# LCDSerialBackpack.net
KiCad netlist of a schematic drawn in EAGLE
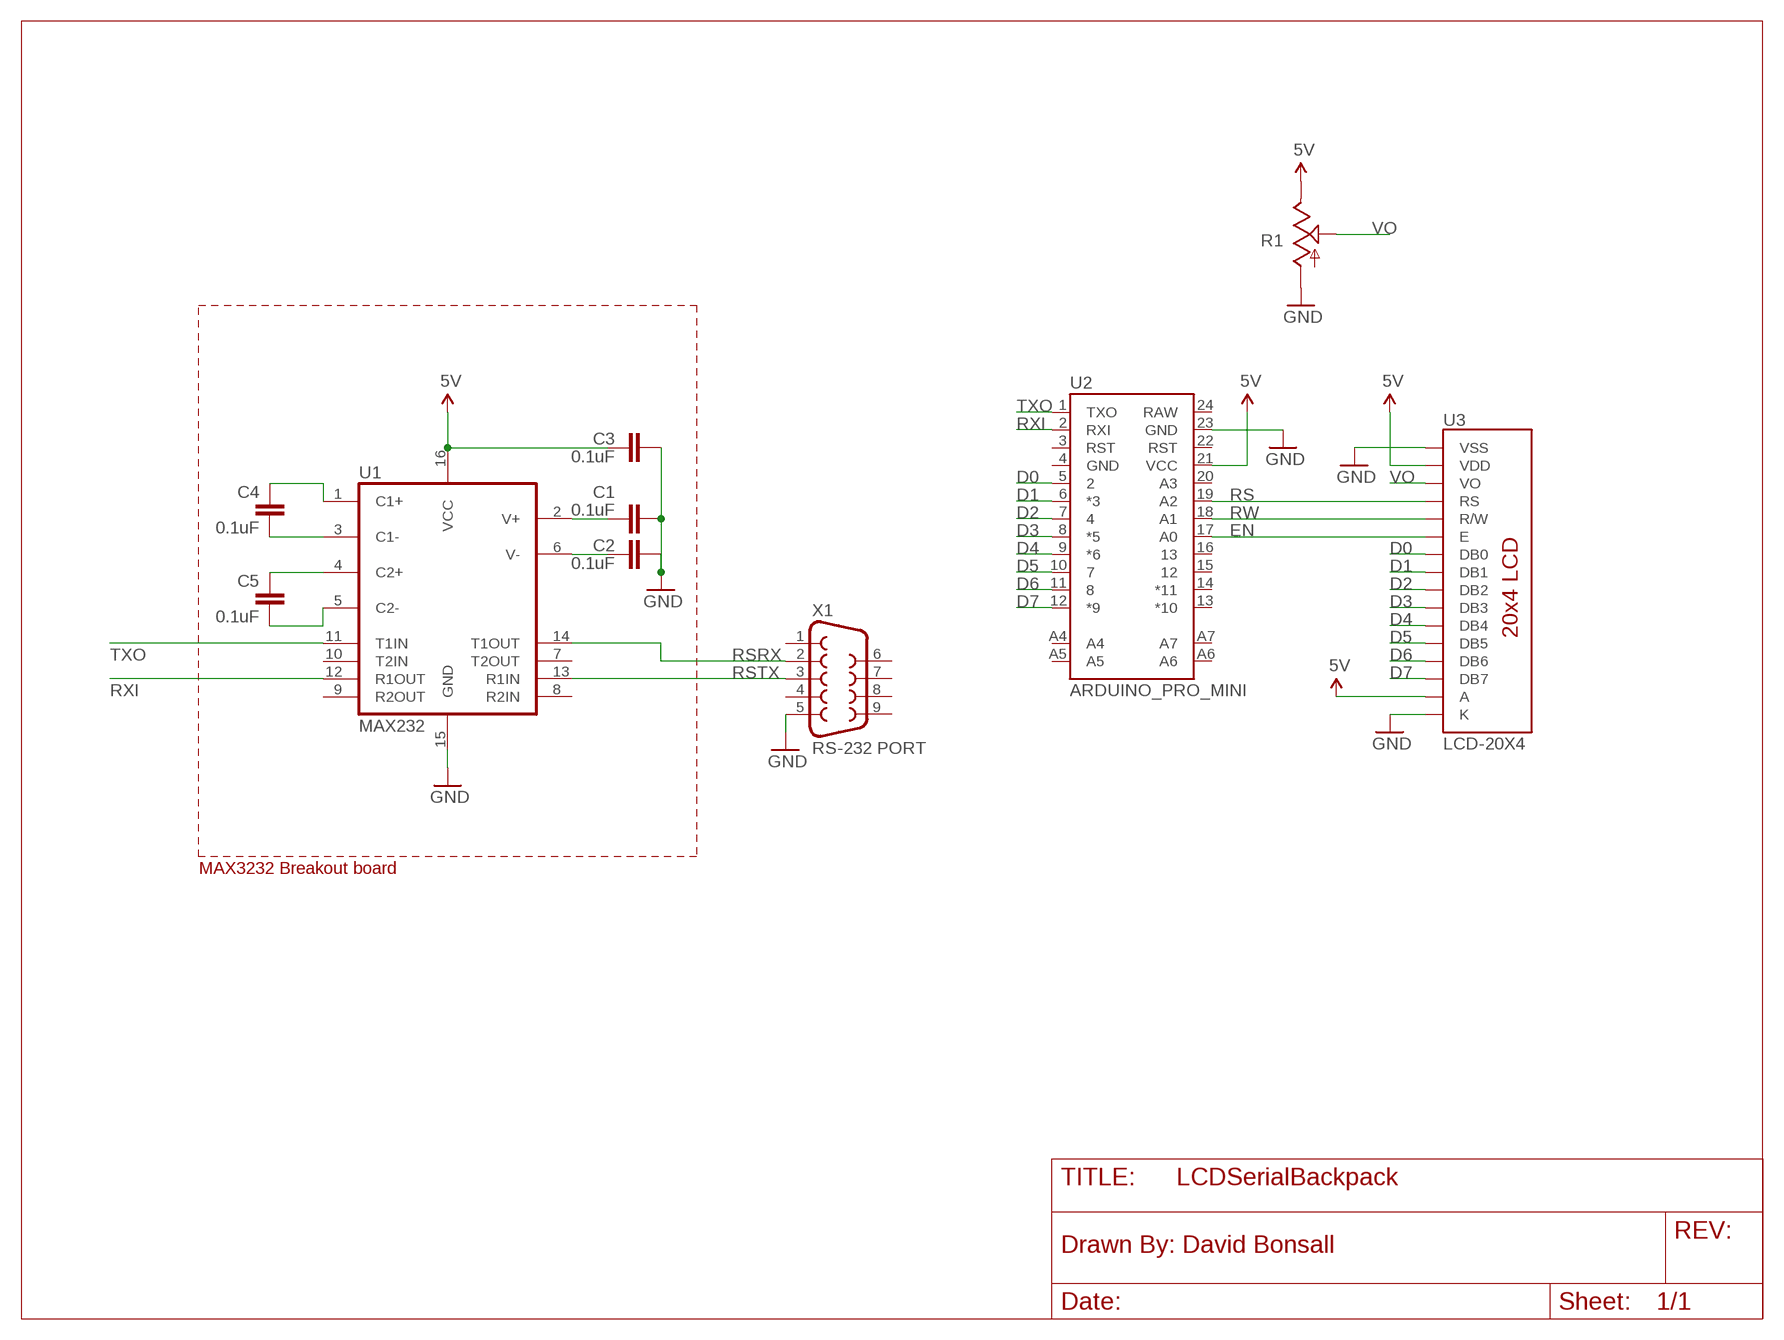
[diagram p0: schematic, sheet 1]

(export (version "E")
  (design (tool "Eeschema 10.0.6"))
  (components
    (comp (ref "C1")
      (value "0.1uF")
      (footprint "eagle-import:0402-CAP")
      (libsource (lib "eagle-import") (part ".1UF-CER"))
    )
    (comp (ref "C2")
      (value "0.1uF")
      (footprint "eagle-import:0402-CAP")
      (libsource (lib "eagle-import") (part ".1UF-CER"))
    )
    (comp (ref "C3")
      (value "0.1uF")
      (footprint "eagle-import:0402-CAP")
      (libsource (lib "eagle-import") (part ".1UF-CER"))
    )
    (comp (ref "C4")
      (value "0.1uF")
      (footprint "eagle-import:0402-CAP")
      (libsource (lib "eagle-import") (part ".1UF-CER"))
    )
    (comp (ref "C5")
      (value "0.1uF")
      (footprint "eagle-import:0402-CAP")
      (libsource (lib "eagle-import") (part ".1UF-CER"))
    )
    (comp (ref "R1")
      (value "POT100K_3362U")
      (footprint "eagle-import:3362U")
      (libsource (lib "eagle-import") (part "POT100K_3362U"))
    )
    (comp (ref "U1")
      (value "MAX232")
      (footprint "eagle-import:DIL16")
      (libsource (lib "eagle-import") (part "MAX232PTH"))
    )
    (comp (ref "U2")
      (value "ARDUINO_PRO_MINI")
      (footprint "eagle-import:ARDUINO_PRO_MINI")
      (libsource (lib "eagle-import") (part "ARDUINO_PRO_MINI"))
    )
    (comp (ref "U3")
      (value "LCD-20X4")
      (footprint "eagle-import:LCD-16X2")
      (libsource (lib "eagle-import") (part "LCD-16X2SILK"))
    )
    (comp (ref "X1")
      (value "RS-232 PORT")
      (footprint "eagle-import:DB9")
      (libsource (lib "eagle-import") (part "DB9FEMALE"))
    )
  )
  (nets
    (net (code "1") (name "/D0") (class "Default")
      (node (ref "U2") (pin "5") (pinfunction "2_5") (pintype "bidirectional"))
      (node (ref "U3") (pin "7") (pinfunction "DB0_7") (pintype "bidirectional"))
    )
    (net (code "2") (name "/D1") (class "Default")
      (node (ref "U2") (pin "6") (pinfunction "*3_6") (pintype "bidirectional"))
      (node (ref "U3") (pin "8") (pinfunction "DB1_8") (pintype "bidirectional"))
    )
    (net (code "3") (name "/D2") (class "Default")
      (node (ref "U2") (pin "7") (pinfunction "4_7") (pintype "bidirectional"))
      (node (ref "U3") (pin "9") (pinfunction "DB2_9") (pintype "bidirectional"))
    )
    (net (code "4") (name "/D3") (class "Default")
      (node (ref "U2") (pin "8") (pinfunction "*5_8") (pintype "bidirectional"))
      (node (ref "U3") (pin "10") (pinfunction "DB3_10") (pintype "bidirectional"))
    )
    (net (code "5") (name "/D4") (class "Default")
      (node (ref "U2") (pin "9") (pinfunction "*6_9") (pintype "bidirectional"))
      (node (ref "U3") (pin "11") (pinfunction "DB4_11") (pintype "bidirectional"))
    )
    (net (code "6") (name "/D5") (class "Default")
      (node (ref "U2") (pin "10") (pinfunction "7_10") (pintype "bidirectional"))
      (node (ref "U3") (pin "12") (pinfunction "DB5_12") (pintype "bidirectional"))
    )
    (net (code "7") (name "/D6") (class "Default")
      (node (ref "U2") (pin "11") (pinfunction "8_11") (pintype "bidirectional"))
      (node (ref "U3") (pin "13") (pinfunction "DB6_13") (pintype "bidirectional"))
    )
    (net (code "8") (name "/D7") (class "Default")
      (node (ref "U2") (pin "12") (pinfunction "*9_12") (pintype "bidirectional"))
      (node (ref "U3") (pin "14") (pinfunction "DB7_14") (pintype "bidirectional"))
    )
    (net (code "9") (name "/EN") (class "Default")
      (node (ref "U2") (pin "17") (pinfunction "A0_17") (pintype "bidirectional"))
      (node (ref "U3") (pin "6") (pinfunction "E_6") (pintype "input"))
    )
    (net (code "10") (name "/RS") (class "Default")
      (node (ref "U2") (pin "19") (pinfunction "A2_19") (pintype "bidirectional"))
      (node (ref "U3") (pin "4") (pinfunction "RS_4") (pintype "input"))
    )
    (net (code "11") (name "/RSRX") (class "Default")
      (node (ref "U1") (pin "14") (pinfunction "T1OUT_14") (pintype "output"))
      (node (ref "X1") (pin "2") (pinfunction "2_2") (pintype "passive"))
    )
    (net (code "12") (name "/RSTX") (class "Default")
      (node (ref "U1") (pin "13") (pinfunction "R1IN_13") (pintype "input"))
      (node (ref "X1") (pin "3") (pinfunction "3_3") (pintype "passive"))
    )
    (net (code "13") (name "/RW") (class "Default")
      (node (ref "U2") (pin "18") (pinfunction "A1_18") (pintype "bidirectional"))
      (node (ref "U3") (pin "5") (pinfunction "R/W_5") (pintype "input"))
    )
    (net (code "14") (name "/RXI") (class "Default")
      (node (ref "U1") (pin "12") (pinfunction "R1OUT_12") (pintype "output"))
      (node (ref "U2") (pin "2") (pinfunction "RXI_2") (pintype "bidirectional"))
    )
    (net (code "15") (name "/TXO") (class "Default")
      (node (ref "U1") (pin "11") (pinfunction "T1IN_11") (pintype "input"))
      (node (ref "U2") (pin "1") (pinfunction "TXO_1") (pintype "bidirectional"))
    )
    (net (code "16") (name "/VO") (class "Default")
      (node (ref "R1") (pin "P$2") (pinfunction "S_P$2") (pintype "passive"))
      (node (ref "U3") (pin "3") (pinfunction "VO_3") (pintype "bidirectional"))
    )
    (net (code "17") (name "5V") (class "Default")
      (node (ref "C3") (pin "1") (pinfunction "1_1") (pintype "passive"))
      (node (ref "R1") (pin "P$1") (pinfunction "E_P$1") (pintype "passive"))
      (node (ref "U1") (pin "16") (pinfunction "VCC_16") (pintype "bidirectional"))
      (node (ref "U2") (pin "21") (pinfunction "VCC_21") (pintype "bidirectional"))
      (node (ref "U3") (pin "15") (pinfunction "A_15") (pintype "power_in"))
      (node (ref "U3") (pin "2") (pinfunction "VDD_2") (pintype "power_in"))
    )
    (net (code "18") (name "GND") (class "Default")
      (node (ref "C1") (pin "2") (pinfunction "2_2") (pintype "passive"))
      (node (ref "C2") (pin "2") (pinfunction "2_2") (pintype "passive"))
      (node (ref "C3") (pin "2") (pinfunction "2_2") (pintype "passive"))
      (node (ref "R1") (pin "P$3") (pinfunction "A_P$3") (pintype "passive"))
      (node (ref "U1") (pin "15") (pinfunction "GND_15") (pintype "bidirectional"))
      (node (ref "U2") (pin "23") (pinfunction "GND_23") (pintype "bidirectional"))
      (node (ref "U3") (pin "1") (pinfunction "VSS_1") (pintype "power_in"))
      (node (ref "U3") (pin "16") (pinfunction "K_16") (pintype "power_in"))
      (node (ref "X1") (pin "5") (pinfunction "5_5") (pintype "passive"))
    )
    (net (code "19") (name "Net-(U1-C1+)") (class "Default")
      (node (ref "C4") (pin "2") (pinfunction "2_2") (pintype "passive"))
      (node (ref "U1") (pin "1") (pinfunction "C1+_1") (pintype "bidirectional"))
    )
    (net (code "20") (name "Net-(U1-C1-)") (class "Default")
      (node (ref "C4") (pin "1") (pinfunction "1_1") (pintype "passive"))
      (node (ref "U1") (pin "3") (pinfunction "C1-_3") (pintype "bidirectional"))
    )
    (net (code "21") (name "Net-(U1-C2+)") (class "Default")
      (node (ref "C5") (pin "2") (pinfunction "2_2") (pintype "passive"))
      (node (ref "U1") (pin "4") (pinfunction "C2+_4") (pintype "bidirectional"))
    )
    (net (code "22") (name "Net-(U1-C2-)") (class "Default")
      (node (ref "C5") (pin "1") (pinfunction "1_1") (pintype "passive"))
      (node (ref "U1") (pin "5") (pinfunction "C2-_5") (pintype "bidirectional"))
    )
    (net (code "23") (name "Net-(U1-V+)") (class "Default")
      (node (ref "C1") (pin "1") (pinfunction "1_1") (pintype "passive"))
      (node (ref "U1") (pin "2") (pinfunction "V+_2") (pintype "bidirectional"))
    )
    (net (code "24") (name "Net-(U1-V-)") (class "Default")
      (node (ref "C2") (pin "1") (pinfunction "1_1") (pintype "passive"))
      (node (ref "U1") (pin "6") (pinfunction "V-_6") (pintype "bidirectional"))
    )
    (net (code "25") (name "unconnected-(U1-R2IN-Pad8)") (class "Default")
      (node (ref "U1") (pin "8") (pinfunction "R2IN_8") (pintype "input"))
    )
    (net (code "26") (name "unconnected-(U1-R2OUT-Pad9)") (class "Default")
      (node (ref "U1") (pin "9") (pinfunction "R2OUT_9") (pintype "output"))
    )
    (net (code "27") (name "unconnected-(U1-T2IN-Pad10)") (class "Default")
      (node (ref "U1") (pin "10") (pinfunction "T2IN_10") (pintype "input"))
    )
    (net (code "28") (name "unconnected-(U1-T2OUT-Pad7)") (class "Default")
      (node (ref "U1") (pin "7") (pinfunction "T2OUT_7") (pintype "output"))
    )
    (net (code "29") (name "unconnected-(U2-*10-Pad13)") (class "Default")
      (node (ref "U2") (pin "13") (pinfunction "*10_13") (pintype "bidirectional"))
    )
    (net (code "30") (name "unconnected-(U2-*11-Pad14)") (class "Default")
      (node (ref "U2") (pin "14") (pinfunction "*11_14") (pintype "bidirectional"))
    )
    (net (code "31") (name "unconnected-(U2-12-Pad15)") (class "Default")
      (node (ref "U2") (pin "15") (pinfunction "12_15") (pintype "bidirectional"))
    )
    (net (code "32") (name "unconnected-(U2-13-Pad16)") (class "Default")
      (node (ref "U2") (pin "16") (pinfunction "13_16") (pintype "bidirectional"))
    )
    (net (code "33") (name "unconnected-(U2-A3-Pad20)") (class "Default")
      (node (ref "U2") (pin "20") (pinfunction "A3_20") (pintype "bidirectional"))
    )
    (net (code "34") (name "unconnected-(U2-GND-Pad4)") (class "Default")
      (node (ref "U2") (pin "4") (pinfunction "GND_4") (pintype "bidirectional"))
    )
    (net (code "35") (name "unconnected-(U2-PadA4)") (class "Default")
      (node (ref "U2") (pin "A4") (pinfunction "A4_A4") (pintype "bidirectional"))
    )
    (net (code "36") (name "unconnected-(U2-PadA5)") (class "Default")
      (node (ref "U2") (pin "A5") (pinfunction "A5_A5") (pintype "bidirectional"))
    )
    (net (code "37") (name "unconnected-(U2-PadA6)") (class "Default")
      (node (ref "U2") (pin "A6") (pinfunction "A6_A6") (pintype "bidirectional"))
    )
    (net (code "38") (name "unconnected-(U2-PadA7)") (class "Default")
      (node (ref "U2") (pin "A7") (pinfunction "A7_A7") (pintype "bidirectional"))
    )
    (net (code "39") (name "unconnected-(U2-RAW-Pad24)") (class "Default")
      (node (ref "U2") (pin "24") (pinfunction "RAW_24") (pintype "bidirectional"))
    )
    (net (code "40") (name "unconnected-(U2-RST-Pad3)") (class "Default")
      (node (ref "U2") (pin "3") (pinfunction "RST_3") (pintype "bidirectional"))
    )
    (net (code "41") (name "unconnected-(U2-RST-Pad22)") (class "Default")
      (node (ref "U2") (pin "22") (pinfunction "RST_22") (pintype "bidirectional"))
    )
    (net (code "42") (name "unconnected-(X1-Pad1)") (class "Default")
      (node (ref "X1") (pin "1") (pinfunction "1_1") (pintype "passive"))
    )
    (net (code "43") (name "unconnected-(X1-Pad4)") (class "Default")
      (node (ref "X1") (pin "4") (pinfunction "4_4") (pintype "passive"))
    )
    (net (code "44") (name "unconnected-(X1-Pad6)") (class "Default")
      (node (ref "X1") (pin "6") (pinfunction "6_6") (pintype "passive"))
    )
    (net (code "45") (name "unconnected-(X1-Pad7)") (class "Default")
      (node (ref "X1") (pin "7") (pinfunction "7_7") (pintype "passive"))
    )
    (net (code "46") (name "unconnected-(X1-Pad8)") (class "Default")
      (node (ref "X1") (pin "8") (pinfunction "8_8") (pintype "passive"))
    )
    (net (code "47") (name "unconnected-(X1-Pad9)") (class "Default")
      (node (ref "X1") (pin "9") (pinfunction "9_9") (pintype "passive"))
    )
  )
)
